# conductivity.net
KiCad netlist of a schematic drawn in EAGLE
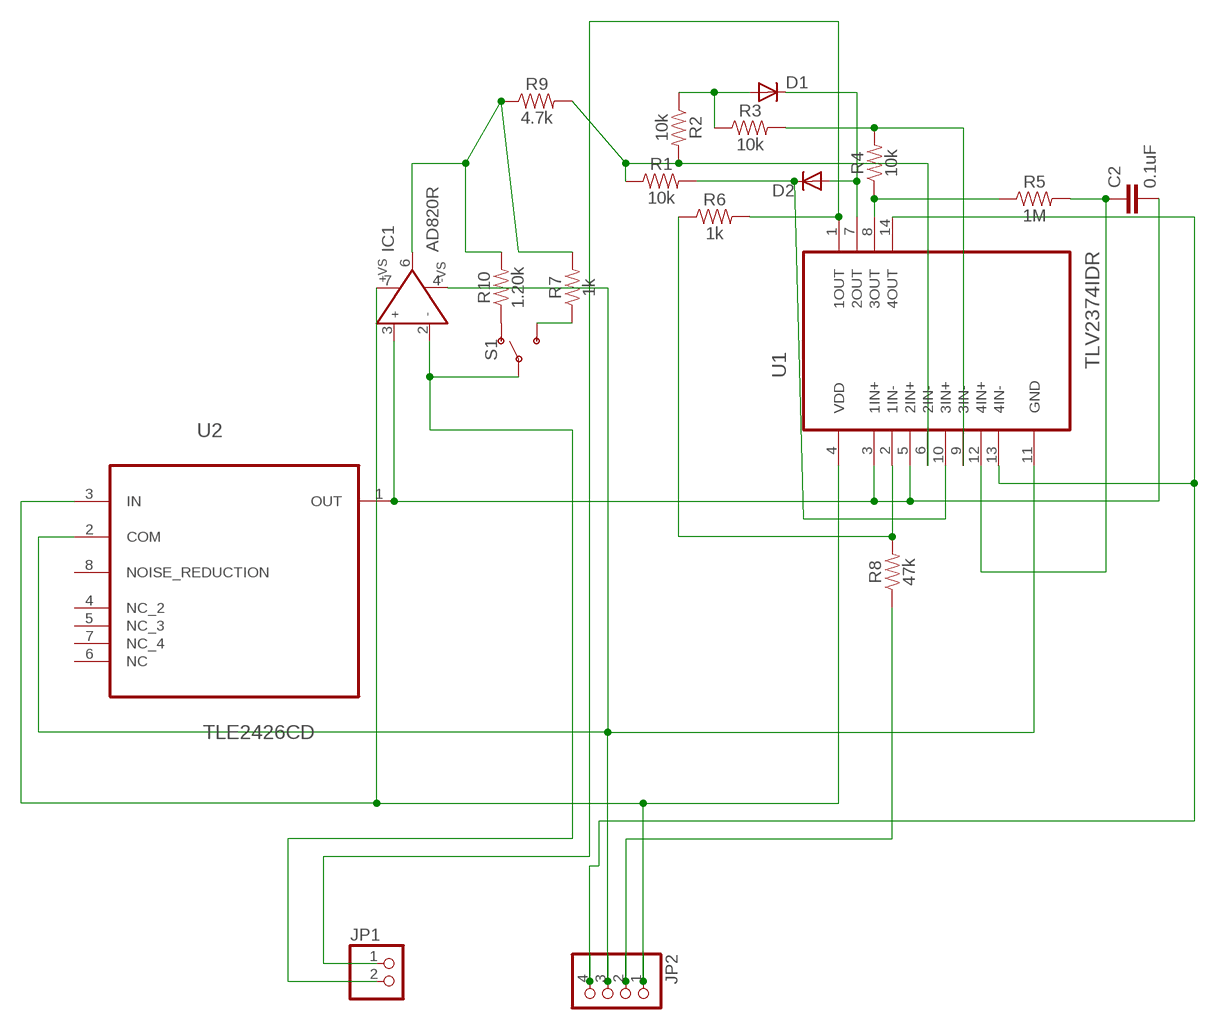
[diagram p0: schematic, sheet 1]

(export (version "E")
  (design (tool "Eeschema 10.0.6"))
  (components
    (comp (ref "C2")
      (value "0.1uF")
      (footprint "eagle-import:0603")
      (libsource (lib "eagle-import") (part "0.1UF-0603-25V-5%"))
    )
    (comp (ref "D1")
      (value "DIODESOD123")
      (footprint "eagle-import:SOD123")
      (libsource (lib "eagle-import") (part "DIODESOD123"))
    )
    (comp (ref "D2")
      (value "DIODESOD123")
      (footprint "eagle-import:SOD123")
      (libsource (lib "eagle-import") (part "DIODESOD123"))
    )
    (comp (ref "IC1")
      (value "AD820R")
      (footprint "eagle-import:SO8")
      (fields (field (name "MF") "Analog Devices") (field (name "MP") "AD820"))
      (libsource (lib "eagle-import") (part "AD820R"))
    )
    (comp (ref "JP1")
      (value "PINHD-1X2")
      (footprint "eagle-import:1X02")
      (libsource (lib "eagle-import") (part "PINHD-1X2"))
    )
    (comp (ref "JP2")
      (value "PINHD-1X4")
      (footprint "eagle-import:1X04")
      (libsource (lib "eagle-import") (part "PINHD-1X4"))
    )
    (comp (ref "R1")
      (value "10k")
      (footprint "eagle-import:0603")
      (libsource (lib "eagle-import") (part "10KOHM-0603-1/10W-1%"))
    )
    (comp (ref "R2")
      (value "10k")
      (footprint "eagle-import:0603")
      (libsource (lib "eagle-import") (part "10KOHM-0603-1/10W-1%"))
    )
    (comp (ref "R3")
      (value "10k")
      (footprint "eagle-import:0603")
      (libsource (lib "eagle-import") (part "10KOHM-0603-1/10W-1%"))
    )
    (comp (ref "R4")
      (value "10k")
      (footprint "eagle-import:0603")
      (libsource (lib "eagle-import") (part "10KOHM-0603-1/10W-1%"))
    )
    (comp (ref "R5")
      (value "1M")
      (footprint "eagle-import:0603")
      (libsource (lib "eagle-import") (part "1MOHM-0603-1/4W-5%"))
    )
    (comp (ref "R6")
      (value "1k")
      (footprint "eagle-import:0603")
      (libsource (lib "eagle-import") (part "1KOHM-0603-1/10W-1%"))
    )
    (comp (ref "R7")
      (value "1k")
      (footprint "eagle-import:0603")
      (libsource (lib "eagle-import") (part "1KOHM-0603-1/10W-1%"))
    )
    (comp (ref "R8")
      (value "47k")
      (footprint "eagle-import:0603")
      (libsource (lib "eagle-import") (part "47KOHM-0603-1/10W-1%"))
    )
    (comp (ref "R9")
      (value "4.7k")
      (footprint "eagle-import:0603")
      (libsource (lib "eagle-import") (part "4.7KOHM-0603-1/10W-1%"))
    )
    (comp (ref "R10")
      (value "1.20k")
      (footprint "eagle-import:0603")
      (libsource (lib "eagle-import") (part "1.20KOHM-0603-1/10W-1%"))
    )
    (comp (ref "S1")
      (value "SWITCH-SPDT-SMD-AYZ0202")
      (footprint "eagle-import:SWITCH_DPDT_SMD_AYZ0202")
      (libsource (lib "eagle-import") (part "SWITCH-SPDT-SMD-AYZ0202"))
    )
    (comp (ref "U1")
      (value "TLV2374IDR")
      (footprint "eagle-import:SOIC127P600X175-14N")
      (fields (field (name "MF") "Texas Instruments"))
      (libsource (lib "eagle-import") (part "TLV2374IDR"))
    )
    (comp (ref "U2")
      (value "TLE2426CD")
      (footprint "eagle-import:SOIC127P600X175-8N")
      (fields (field (name "MF") "Texas Instruments"))
      (libsource (lib "eagle-import") (part "TLE2426CD"))
    )
  )
  (nets
    (net (code "1") (name "Net-(D1-A)") (class "Default")
      (node (ref "D1") (pin "ANODE") (pinfunction "A_ANODE") (pintype "passive"))
      (node (ref "R2") (pin "1") (pinfunction "1_1") (pintype "passive"))
      (node (ref "R3") (pin "1") (pinfunction "1_1") (pintype "passive"))
    )
    (net (code "2") (name "Net-(D1-C)") (class "Default")
      (node (ref "D1") (pin "CATHODE") (pinfunction "C_CATHODE") (pintype "passive"))
      (node (ref "D2") (pin "ANODE") (pinfunction "A_ANODE") (pintype "passive"))
      (node (ref "U1") (pin "7") (pinfunction "2OUT_7") (pintype "output"))
    )
    (net (code "3") (name "Net-(D2-C)") (class "Default")
      (node (ref "D2") (pin "CATHODE") (pinfunction "C_CATHODE") (pintype "passive"))
      (node (ref "R1") (pin "2") (pinfunction "2_2") (pintype "passive"))
      (node (ref "U1") (pin "10") (pinfunction "3IN+_10") (pintype "input"))
    )
    (net (code "4") (name "Net-(IC1-+VS)") (class "Default")
      (node (ref "IC1") (pin "7") (pinfunction "+VS_7") (pintype "input"))
      (node (ref "JP2") (pin "1") (pinfunction "1_1") (pintype "passive"))
      (node (ref "U1") (pin "4") (pinfunction "VDD_4") (pintype "power_in"))
      (node (ref "U2") (pin "3") (pinfunction "IN_3") (pintype "input"))
    )
    (net (code "5") (name "Net-(IC1--VS)") (class "Default")
      (node (ref "IC1") (pin "4") (pinfunction "-VS_4") (pintype "input"))
      (node (ref "JP2") (pin "3") (pinfunction "3_3") (pintype "passive"))
      (node (ref "U1") (pin "11") (pinfunction "GND_11") (pintype "passive"))
      (node (ref "U2") (pin "2") (pinfunction "COM_2") (pintype "passive"))
    )
    (net (code "6") (name "Net-(IC1-IN+)") (class "Default")
      (node (ref "C2") (pin "2") (pinfunction "2_2") (pintype "passive"))
      (node (ref "IC1") (pin "3") (pinfunction "IN+_3") (pintype "input"))
      (node (ref "U1") (pin "3") (pinfunction "1IN+_3") (pintype "input"))
      (node (ref "U1") (pin "5") (pinfunction "2IN+_5") (pintype "input"))
      (node (ref "U2") (pin "1") (pinfunction "OUT_1") (pintype "output"))
    )
    (net (code "7") (name "Net-(IC1-IN-)") (class "Default")
      (node (ref "IC1") (pin "2") (pinfunction "IN-_2") (pintype "input"))
      (node (ref "JP1") (pin "2") (pinfunction "2_2") (pintype "passive"))
      (node (ref "S1") (pin "2") (pinfunction "P_2") (pintype "passive"))
    )
    (net (code "8") (name "Net-(IC1-OUT)") (class "Default")
      (node (ref "IC1") (pin "6") (pinfunction "OUT_6") (pintype "output"))
      (node (ref "R10") (pin "2") (pinfunction "2_2") (pintype "passive"))
      (node (ref "R7") (pin "2") (pinfunction "2_2") (pintype "passive"))
      (node (ref "R9") (pin "1") (pinfunction "1_1") (pintype "passive"))
    )
    (net (code "9") (name "Net-(JP2-Pad2)") (class "Default")
      (node (ref "JP2") (pin "2") (pinfunction "2_2") (pintype "passive"))
      (node (ref "R8") (pin "1") (pinfunction "1_1") (pintype "passive"))
    )
    (net (code "10") (name "Net-(S1-O)") (class "Default")
      (node (ref "R10") (pin "1") (pinfunction "1_1") (pintype "passive"))
      (node (ref "S1") (pin "1") (pinfunction "O_1") (pintype "passive"))
    )
    (net (code "11") (name "Net-(S1-S)") (class "Default")
      (node (ref "R7") (pin "1") (pinfunction "1_1") (pintype "passive"))
      (node (ref "S1") (pin "3") (pinfunction "S_3") (pintype "passive"))
    )
    (net (code "12") (name "Net-(U1-1IN-)") (class "Default")
      (node (ref "R6") (pin "1") (pinfunction "1_1") (pintype "passive"))
      (node (ref "R8") (pin "2") (pinfunction "2_2") (pintype "passive"))
      (node (ref "U1") (pin "2") (pinfunction "1IN-_2") (pintype "input"))
    )
    (net (code "13") (name "Net-(U1-1OUT)") (class "Default")
      (node (ref "JP1") (pin "1") (pinfunction "1_1") (pintype "passive"))
      (node (ref "R6") (pin "2") (pinfunction "2_2") (pintype "passive"))
      (node (ref "U1") (pin "1") (pinfunction "1OUT_1") (pintype "output"))
    )
    (net (code "14") (name "Net-(U1-2IN-)") (class "Default")
      (node (ref "R1") (pin "1") (pinfunction "1_1") (pintype "passive"))
      (node (ref "R2") (pin "2") (pinfunction "2_2") (pintype "passive"))
      (node (ref "R9") (pin "2") (pinfunction "2_2") (pintype "passive"))
      (node (ref "U1") (pin "6") (pinfunction "2IN-_6") (pintype "input"))
    )
    (net (code "15") (name "Net-(U1-3IN-)") (class "Default")
      (node (ref "R3") (pin "2") (pinfunction "2_2") (pintype "passive"))
      (node (ref "R4") (pin "2") (pinfunction "2_2") (pintype "passive"))
      (node (ref "U1") (pin "9") (pinfunction "3IN-_9") (pintype "input"))
    )
    (net (code "16") (name "Net-(U1-3OUT)") (class "Default")
      (node (ref "R4") (pin "1") (pinfunction "1_1") (pintype "passive"))
      (node (ref "R5") (pin "1") (pinfunction "1_1") (pintype "passive"))
      (node (ref "U1") (pin "8") (pinfunction "3OUT_8") (pintype "output"))
    )
    (net (code "17") (name "Net-(U1-4IN+)") (class "Default")
      (node (ref "C2") (pin "1") (pinfunction "1_1") (pintype "passive"))
      (node (ref "R5") (pin "2") (pinfunction "2_2") (pintype "passive"))
      (node (ref "U1") (pin "12") (pinfunction "4IN+_12") (pintype "input"))
    )
    (net (code "18") (name "Net-(U1-4IN-)") (class "Default")
      (node (ref "JP2") (pin "4") (pinfunction "4_4") (pintype "passive"))
      (node (ref "U1") (pin "13") (pinfunction "4IN-_13") (pintype "input"))
      (node (ref "U1") (pin "14") (pinfunction "4OUT_14") (pintype "output"))
    )
    (net (code "19") (name "unconnected-(U2-NC-Pad6)") (class "Default")
      (node (ref "U2") (pin "6") (pinfunction "NC_6") (pintype "no_connect"))
    )
    (net (code "20") (name "unconnected-(U2-NC_2-Pad4)") (class "Default")
      (node (ref "U2") (pin "4") (pinfunction "NC_2_4") (pintype "no_connect"))
    )
    (net (code "21") (name "unconnected-(U2-NC_3-Pad5)") (class "Default")
      (node (ref "U2") (pin "5") (pinfunction "NC_3_5") (pintype "no_connect"))
    )
    (net (code "22") (name "unconnected-(U2-NC_4-Pad7)") (class "Default")
      (node (ref "U2") (pin "7") (pinfunction "NC_4_7") (pintype "no_connect"))
    )
    (net (code "23") (name "unconnected-(U2-NOISE_REDUCTION-Pad8)") (class "Default")
      (node (ref "U2") (pin "8") (pinfunction "NOISE_REDUCTION_8") (pintype "passive"))
    )
  )
)
